# ADC.net
KiCad netlist of a schematic drawn in Altium Designer
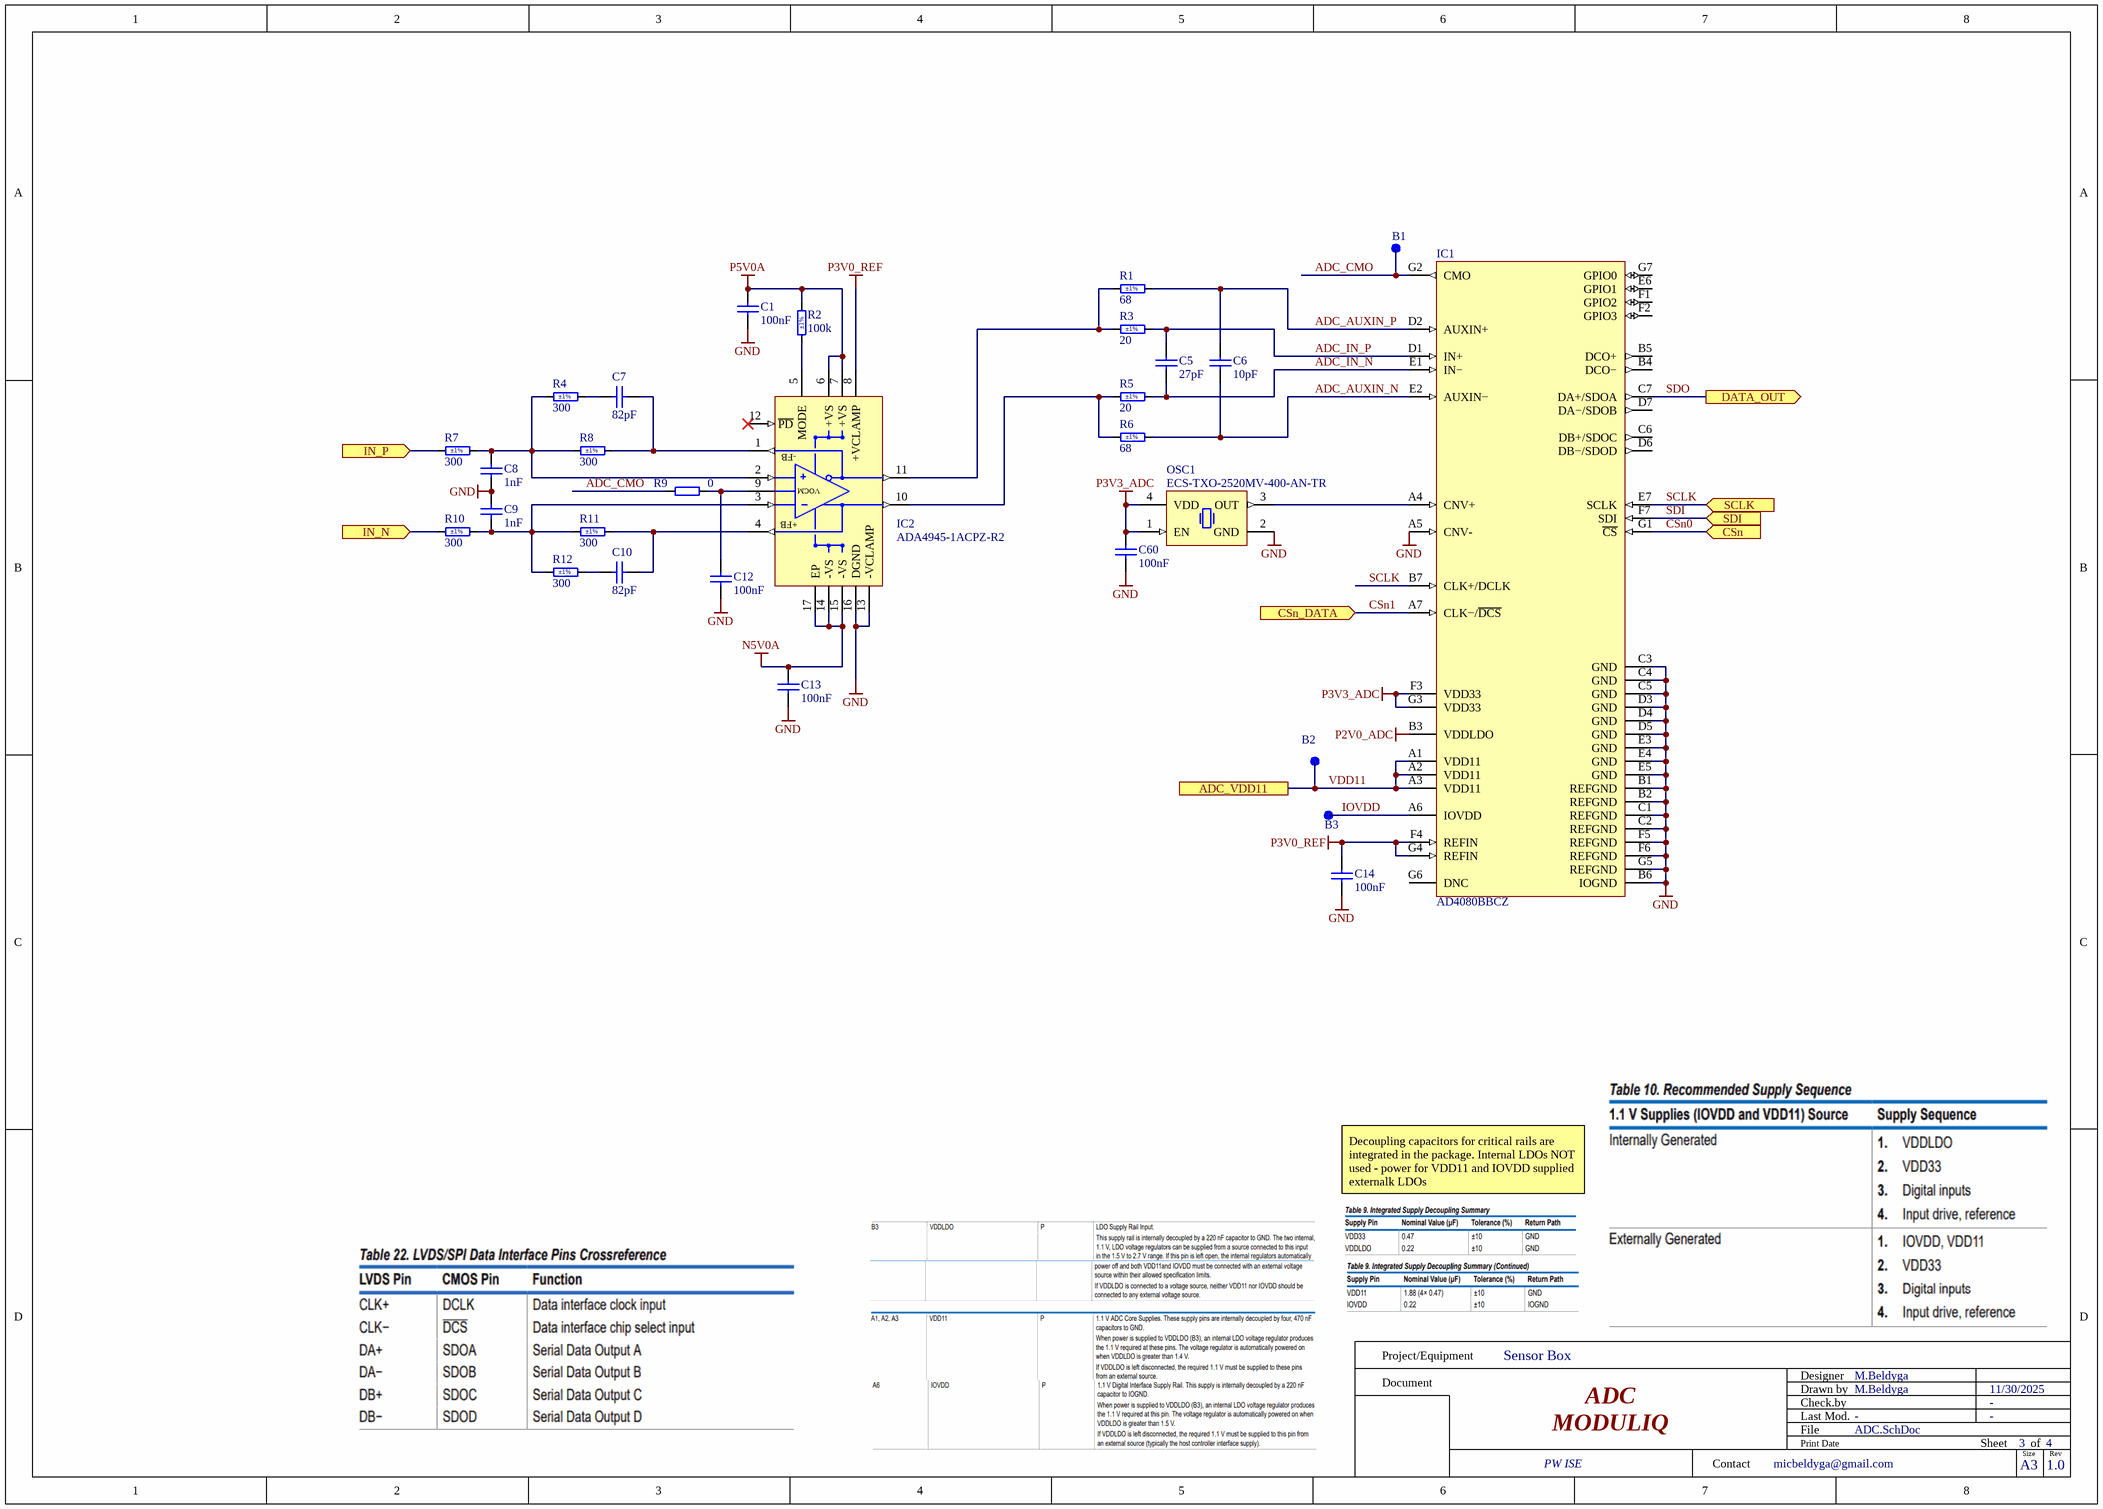
[diagram p0: ADC.SchDoc]

(export (version "E")
  (design (tool "Eeschema 10.0.6"))
  (components
    (comp (ref "B1")
      (value "SMD Pad")
      (footprint "C100")
      (description "Pad")
      (fields (field (name "PART NUMBER") "SMD_PAD_D1MM") (field (name "AUTHOR") "CERN DEM JLC"))
      (libsource (lib "Eletro-mechanical") (part "Single SMD Pad (Round)"))
    )
    (comp (ref "B2")
      (value "SMD Pad")
      (footprint "C100")
      (description "Pad")
      (fields (field (name "PART NUMBER") "SMD_PAD_D1MM") (field (name "AUTHOR") "CERN DEM JLC"))
      (libsource (lib "Eletro-mechanical") (part "Single SMD Pad (Round)"))
    )
    (comp (ref "B3")
      (value "SMD Pad")
      (footprint "C100")
      (description "Pad")
      (fields (field (name "PART NUMBER") "SMD_PAD_D1MM") (field (name "AUTHOR") "CERN DEM JLC"))
      (libsource (lib "Eletro-mechanical") (part "Single SMD Pad (Round)"))
    )
    (comp (ref "C1")
      (value "100nF")
      (footprint "CAPC1005X55N")
      (description "Non-polarised capacitor")
      (fields
        (field (name "PART NUMBER") "CC0402_100NF_50V_10%_X7R")
        (field (name "VOLTAGE") "50V")
        (field (name "AUTHOR") "CERN DEM MR")
      )
      (libsource (lib "Capacitors") (part "Capacitor - non polarized"))
    )
    (comp (ref "C5")
      (value "27pF")
      (footprint "CAPC1005X55N")
      (description "Non-polarised capacitor")
      (fields
        (field (name "PART NUMBER") "CC0402_27PF_50V_5%_C0G")
        (field (name "VOLTAGE") "50V")
        (field (name "AUTHOR") "CERN DEM JLC")
      )
      (libsource (lib "Capacitors") (part "Capacitor - non polarized"))
    )
    (comp (ref "C6")
      (value "10pF")
      (footprint "CAPC1005X55N")
      (description "Non-polarised capacitor")
      (fields
        (field (name "PART NUMBER") "CC0402_10PF_50V_5%_C0G")
        (field (name "VOLTAGE") "50V")
        (field (name "AUTHOR") "CERN DEM JLC")
      )
      (libsource (lib "Capacitors") (part "Capacitor - non polarized"))
    )
    (comp (ref "C7")
      (value "82pF")
      (footprint "CAPC1005X55N")
      (description "Non-polarised capacitor")
      (fields
        (field (name "PART NUMBER") "CC0402_82PF_25V_1%_C0G_KEMET_HiQ-CBR")
        (field (name "VOLTAGE") "25V")
        (field (name "AUTHOR") "CERN DEM MR")
      )
      (libsource (lib "Capacitors") (part "Capacitor - non polarized"))
    )
    (comp (ref "C8")
      (value "1nF")
      (footprint "CAPC1005X55N")
      (description "Non-polarised capacitor")
      (fields
        (field (name "PART NUMBER") "CC0402_1NF_50V_5%_C0G")
        (field (name "VOLTAGE") "50V")
        (field (name "AUTHOR") "CERN DEM BC")
      )
      (libsource (lib "Capacitors") (part "Capacitor - non polarized"))
    )
    (comp (ref "C9")
      (value "1nF")
      (footprint "CAPC1005X55N")
      (description "Non-polarised capacitor")
      (fields
        (field (name "PART NUMBER") "CC0402_1NF_50V_5%_C0G")
        (field (name "VOLTAGE") "50V")
        (field (name "AUTHOR") "CERN DEM BC")
      )
      (libsource (lib "Capacitors") (part "Capacitor - non polarized"))
    )
    (comp (ref "C10")
      (value "82pF")
      (footprint "CAPC1005X55N")
      (description "Non-polarised capacitor")
      (fields
        (field (name "PART NUMBER") "CC0402_82PF_25V_1%_C0G_KEMET_HiQ-CBR")
        (field (name "VOLTAGE") "25V")
        (field (name "AUTHOR") "CERN DEM MR")
      )
      (libsource (lib "Capacitors") (part "Capacitor - non polarized"))
    )
    (comp (ref "C12")
      (value "100nF")
      (footprint "CAPC1005X55N")
      (description "Non-polarised capacitor")
      (fields
        (field (name "PART NUMBER") "CC0402_100NF_50V_10%_X7R")
        (field (name "VOLTAGE") "50V")
        (field (name "AUTHOR") "CERN DEM MR")
      )
      (libsource (lib "Capacitors") (part "Capacitor - non polarized"))
    )
    (comp (ref "C13")
      (value "100nF")
      (footprint "CAPC1005X55N")
      (description "Non-polarised capacitor")
      (fields
        (field (name "PART NUMBER") "CC0402_100NF_50V_10%_X7R")
        (field (name "VOLTAGE") "50V")
        (field (name "AUTHOR") "CERN DEM MR")
      )
      (libsource (lib "Capacitors") (part "Capacitor - non polarized"))
    )
    (comp (ref "C14")
      (value "100nF")
      (footprint "CAPC1005X55N")
      (description "Non-polarised capacitor")
      (fields
        (field (name "PART NUMBER") "CC0402_100NF_50V_10%_X7R")
        (field (name "VOLTAGE") "50V")
        (field (name "AUTHOR") "CERN DEM MR")
      )
      (libsource (lib "Capacitors") (part "Capacitor - non polarized"))
    )
    (comp (ref "C60")
      (value "100nF")
      (footprint "CAPC1005X55N")
      (description "Non-polarised capacitor")
      (fields
        (field (name "PART NUMBER") "CC0402_100NF_50V_10%_X7R")
        (field (name "VOLTAGE") "50V")
        (field (name "AUTHOR") "CERN DEM MR")
      )
      (libsource (lib "Capacitors") (part "Capacitor - non polarized"))
    )
    (comp (ref "IC1")
      (value "AD4080BBCZ")
      (footprint "BGA49C65P7X7_500X500X138")
      (description "20-Bit, 40 MSPS, Differential SAR ADC")
      (fields (field (name "MANUFACTURER") "Analog Devices") (field (name "AUTHOR") "Michal Beldyga"))
      (libsource (lib "Semiconductors") (part "AD4080"))
    )
    (comp (ref "IC2")
      (value "ADA4945-1ACPZ-R2")
      (footprint "QFN50P300X300X80_HS-17N")
      (description "High Speed, ±0.1 µV/˚C Offset Drift, Fully Differential ADC Driver")
      (fields (field (name "MANUFACTURER") "Analog Devices") (field (name "AUTHOR") "Michal Beldyga"))
      (libsource (lib "Semiconductors") (part "ADA4945-1"))
    )
    (comp (ref "OSC1")
      (value "ECS-TXO-2520MV-400-AN-TR")
      (footprint "OSC_QANTEK_QX2")
      (fields (field (name "MANUFACTURER") "ECS International"))
      (libsource (lib "mb") (part "ECS-TXO-2520MV-400-AN-TR"))
    )
    (comp (ref "R1")
      (value "68")
      (footprint "RESC1005X40N")
      (description "Resistor - 1%")
      (fields
        (field (name "TOLERANCE") "±1%")
        (field (name "PART NUMBER") "R0402_68R_1%_0.0625W_100PPM")
        (field (name "POWER") "0.0625W")
        (field (name "AUTHOR") "CERN DEM JLC")
      )
      (libsource (lib "Resistors") (part "Resistor - 1%"))
    )
    (comp (ref "R2")
      (value "100k")
      (footprint "RESC1005X40N")
      (description "Resistor - 1%")
      (fields
        (field (name "TOLERANCE") "±1%")
        (field (name "PART NUMBER") "R0402_100K_1%_0.0625W_100PPM")
        (field (name "POWER") "0.0625W")
        (field (name "AUTHOR") "CERN DEM JLC")
      )
      (libsource (lib "Resistors") (part "Resistor - 1%"))
    )
    (comp (ref "R3")
      (value "20")
      (footprint "RESC1005X40N")
      (description "Resistor - 1%")
      (fields
        (field (name "TOLERANCE") "±1%")
        (field (name "PART NUMBER") "R0402_20R_1%_0.0625W_100PPM")
        (field (name "POWER") "0.0625W")
        (field (name "AUTHOR") "CERN DEM JLC")
      )
      (libsource (lib "Resistors") (part "Resistor - 1%"))
    )
    (comp (ref "R4")
      (value "300")
      (footprint "RESC1005X40N")
      (description "Resistor - 1%")
      (fields
        (field (name "TOLERANCE") "±1%")
        (field (name "PART NUMBER") "R0402_300R_1%_0.0625W_100PPM")
        (field (name "POWER") "0.0625W")
        (field (name "AUTHOR") "CERN DEM JLC")
      )
      (libsource (lib "Resistors") (part "Resistor - 1%"))
    )
    (comp (ref "R5")
      (value "20")
      (footprint "RESC1005X40N")
      (description "Resistor - 1%")
      (fields
        (field (name "TOLERANCE") "±1%")
        (field (name "PART NUMBER") "R0402_20R_1%_0.0625W_100PPM")
        (field (name "POWER") "0.0625W")
        (field (name "AUTHOR") "CERN DEM JLC")
      )
      (libsource (lib "Resistors") (part "Resistor - 1%"))
    )
    (comp (ref "R6")
      (value "68")
      (footprint "RESC1005X40N")
      (description "Resistor - 1%")
      (fields
        (field (name "TOLERANCE") "±1%")
        (field (name "PART NUMBER") "R0402_68R_1%_0.0625W_100PPM")
        (field (name "POWER") "0.0625W")
        (field (name "AUTHOR") "CERN DEM JLC")
      )
      (libsource (lib "Resistors") (part "Resistor - 1%"))
    )
    (comp (ref "R7")
      (value "300")
      (footprint "RESC1005X40N")
      (description "Resistor - 1%")
      (fields
        (field (name "TOLERANCE") "±1%")
        (field (name "PART NUMBER") "R0402_300R_1%_0.0625W_100PPM")
        (field (name "POWER") "0.0625W")
        (field (name "AUTHOR") "CERN DEM JLC")
      )
      (libsource (lib "Resistors") (part "Resistor - 1%"))
    )
    (comp (ref "R8")
      (value "300")
      (footprint "RESC1005X40N")
      (description "Resistor - 1%")
      (fields
        (field (name "TOLERANCE") "±1%")
        (field (name "PART NUMBER") "R0402_300R_1%_0.0625W_100PPM")
        (field (name "POWER") "0.0625W")
        (field (name "AUTHOR") "CERN DEM JLC")
      )
      (libsource (lib "Resistors") (part "Resistor - 1%"))
    )
    (comp (ref "R9")
      (value "0")
      (footprint "RESC1005X40N")
      (description "Resistor")
      (fields
        (field (name "PART NUMBER") "R0402_0R_JUMPER")
        (field (name "MANUFACTURER") "GENERIC")
        (field (name "AUTHOR") "CERN DEM JLC")
      )
      (libsource (lib "Resistors") (part "Resistor"))
    )
    (comp (ref "R10")
      (value "300")
      (footprint "RESC1005X40N")
      (description "Resistor - 1%")
      (fields
        (field (name "TOLERANCE") "±1%")
        (field (name "PART NUMBER") "R0402_300R_1%_0.0625W_100PPM")
        (field (name "POWER") "0.0625W")
        (field (name "AUTHOR") "CERN DEM JLC")
      )
      (libsource (lib "Resistors") (part "Resistor - 1%"))
    )
    (comp (ref "R11")
      (value "300")
      (footprint "RESC1005X40N")
      (description "Resistor - 1%")
      (fields
        (field (name "TOLERANCE") "±1%")
        (field (name "PART NUMBER") "R0402_300R_1%_0.0625W_100PPM")
        (field (name "POWER") "0.0625W")
        (field (name "AUTHOR") "CERN DEM JLC")
      )
      (libsource (lib "Resistors") (part "Resistor - 1%"))
    )
    (comp (ref "R12")
      (value "300")
      (footprint "RESC1005X40N")
      (description "Resistor - 1%")
      (fields
        (field (name "TOLERANCE") "±1%")
        (field (name "PART NUMBER") "R0402_300R_1%_0.0625W_100PPM")
        (field (name "POWER") "0.0625W")
        (field (name "AUTHOR") "CERN DEM JLC")
      )
      (libsource (lib "Resistors") (part "Resistor - 1%"))
    )
  )
  (nets
    (net (code "1") (name "/ADC_AUXIN_N") (class "Default")
      (node (ref "C6") (pin "1") (pinfunction "1_1") (pintype "passive"))
      (node (ref "IC1") (pin "E2") (pinfunction "AUXIN−_E2") (pintype "input"))
      (node (ref "R6") (pin "2") (pinfunction "2_2") (pintype "passive"))
    )
    (net (code "2") (name "/ADC_AUXIN_P") (class "Default")
      (node (ref "C6") (pin "2") (pinfunction "2_2") (pintype "passive"))
      (node (ref "IC1") (pin "D2") (pinfunction "AUXIN+_D2") (pintype "input"))
      (node (ref "R1") (pin "2") (pinfunction "2_2") (pintype "passive"))
    )
    (net (code "3") (name "/ADC_CMO") (class "Default")
      (node (ref "B1") (pin "1") (pinfunction "1_1") (pintype "bidirectional"))
      (node (ref "IC1") (pin "G2") (pinfunction "CMO_G2") (pintype "output"))
      (node (ref "R9") (pin "1") (pinfunction "1_1") (pintype "passive"))
    )
    (net (code "4") (name "/ADC_IN_N") (class "Default")
      (node (ref "C5") (pin "1") (pinfunction "1_1") (pintype "passive"))
      (node (ref "IC1") (pin "E1") (pinfunction "IN−_E1") (pintype "input"))
      (node (ref "R5") (pin "2") (pinfunction "2_2") (pintype "passive"))
    )
    (net (code "5") (name "/ADC_IN_P") (class "Default")
      (node (ref "C5") (pin "2") (pinfunction "2_2") (pintype "passive"))
      (node (ref "IC1") (pin "D1") (pinfunction "IN+_D1") (pintype "input"))
      (node (ref "R3") (pin "2") (pinfunction "2_2") (pintype "passive"))
    )
    (net (code "6") (name "/CSn0") (class "Default")
      (node (ref "IC1") (pin "G1") (pinfunction "~{CS}_G1") (pintype "input"))
    )
    (net (code "7") (name "/CSn1") (class "Default")
      (node (ref "IC1") (pin "A7") (pinfunction "CLK−/~{DCS}_A7") (pintype "input"))
    )
    (net (code "8") (name "/IN_N") (class "Default")
      (node (ref "R10") (pin "1") (pinfunction "1_1") (pintype "passive"))
    )
    (net (code "9") (name "/IN_P") (class "Default")
      (node (ref "R7") (pin "1") (pinfunction "1_1") (pintype "passive"))
    )
    (net (code "10") (name "/IOVDD") (class "Default")
      (node (ref "B3") (pin "1") (pinfunction "1_1") (pintype "bidirectional"))
      (node (ref "IC1") (pin "A6") (pinfunction "IOVDD_A6") (pintype "power_in"))
    )
    (net (code "11") (name "/SCLK") (class "Default")
      (node (ref "IC1") (pin "B7") (pinfunction "CLK+/DCLK_B7") (pintype "input"))
      (node (ref "IC1") (pin "E7") (pinfunction "SCLK_E7") (pintype "input"))
    )
    (net (code "12") (name "/SDI") (class "Default")
      (node (ref "IC1") (pin "F7") (pinfunction "SDI_F7") (pintype "input"))
    )
    (net (code "13") (name "/SDO") (class "Default")
      (node (ref "IC1") (pin "C7") (pinfunction "DA+/SDOA_C7") (pintype "output"))
    )
    (net (code "14") (name "/VDD11") (class "Default")
      (node (ref "B2") (pin "1") (pinfunction "1_1") (pintype "bidirectional"))
      (node (ref "IC1") (pin "A1") (pinfunction "VDD11_A1") (pintype "power_in"))
      (node (ref "IC1") (pin "A2") (pinfunction "VDD11_A2") (pintype "power_in"))
      (node (ref "IC1") (pin "A3") (pinfunction "VDD11_A3") (pintype "power_in"))
    )
    (net (code "15") (name "GND") (class "Default")
      (node (ref "C1") (pin "1") (pinfunction "1_1") (pintype "passive"))
      (node (ref "C12") (pin "1") (pinfunction "1_1") (pintype "passive"))
      (node (ref "C13") (pin "1") (pinfunction "1_1") (pintype "passive"))
      (node (ref "C14") (pin "1") (pinfunction "1_1") (pintype "passive"))
      (node (ref "C60") (pin "1") (pinfunction "1_1") (pintype "passive"))
      (node (ref "C8") (pin "1") (pinfunction "1_1") (pintype "passive"))
      (node (ref "C9") (pin "2") (pinfunction "2_2") (pintype "passive"))
      (node (ref "IC1") (pin "A5") (pinfunction "CNV-_A5") (pintype "input"))
      (node (ref "IC1") (pin "B1") (pinfunction "REFGND_B1") (pintype "power_in"))
      (node (ref "IC1") (pin "B2") (pinfunction "REFGND_B2") (pintype "power_in"))
      (node (ref "IC1") (pin "B6") (pinfunction "IOGND_B6") (pintype "power_in"))
      (node (ref "IC1") (pin "C1") (pinfunction "REFGND_C1") (pintype "power_in"))
      (node (ref "IC1") (pin "C2") (pinfunction "REFGND_C2") (pintype "power_in"))
      (node (ref "IC1") (pin "C3") (pinfunction "GND_C3") (pintype "power_in"))
      (node (ref "IC1") (pin "C4") (pinfunction "GND_C4") (pintype "power_in"))
      (node (ref "IC1") (pin "C5") (pinfunction "GND_C5") (pintype "power_in"))
      (node (ref "IC1") (pin "D3") (pinfunction "GND_D3") (pintype "power_in"))
      (node (ref "IC1") (pin "D4") (pinfunction "GND_D4") (pintype "power_in"))
      (node (ref "IC1") (pin "D5") (pinfunction "GND_D5") (pintype "power_in"))
      (node (ref "IC1") (pin "E3") (pinfunction "GND_E3") (pintype "power_in"))
      (node (ref "IC1") (pin "E4") (pinfunction "GND_E4") (pintype "power_in"))
      (node (ref "IC1") (pin "E5") (pinfunction "GND_E5") (pintype "power_in"))
      (node (ref "IC1") (pin "F5") (pinfunction "REFGND_F5") (pintype "power_in"))
      (node (ref "IC1") (pin "F6") (pinfunction "REFGND_F6") (pintype "power_in"))
      (node (ref "IC1") (pin "G5") (pinfunction "REFGND_G5") (pintype "power_in"))
      (node (ref "IC2") (pin "13") (pinfunction "-VCLAMP_13") (pintype "power_in"))
      (node (ref "IC2") (pin "16") (pinfunction "DGND_16") (pintype "power_in"))
      (node (ref "OSC1") (pin "2") (pinfunction "GND_2") (pintype "power_in"))
    )
    (net (code "16") (name "N5V0A") (class "Default")
      (node (ref "C13") (pin "2") (pinfunction "2_2") (pintype "passive"))
      (node (ref "IC2") (pin "14") (pinfunction "-VS_14") (pintype "power_in"))
      (node (ref "IC2") (pin "15") (pinfunction "-VS_15") (pintype "power_in"))
      (node (ref "IC2") (pin "17") (pinfunction "EP_17") (pintype "power_in"))
    )
    (net (code "17") (name "Net-(C7-Pad1)") (class "Default")
      (node (ref "C7") (pin "1") (pinfunction "1_1") (pintype "passive"))
      (node (ref "R4") (pin "2") (pinfunction "2_2") (pintype "passive"))
    )
    (net (code "18") (name "Net-(C10-Pad1)") (class "Default")
      (node (ref "C10") (pin "1") (pinfunction "1_1") (pintype "passive"))
      (node (ref "R12") (pin "2") (pinfunction "2_2") (pintype "passive"))
    )
    (net (code "19") (name "Net-(IC1-CNV+)") (class "Default")
      (node (ref "IC1") (pin "A4") (pinfunction "CNV+_A4") (pintype "input"))
      (node (ref "OSC1") (pin "3") (pinfunction "OUT_3") (pintype "output"))
    )
    (net (code "20") (name "Net-(IC2-+FB)") (class "Default")
      (node (ref "C10") (pin "2") (pinfunction "2_2") (pintype "passive"))
      (node (ref "IC2") (pin "4") (pinfunction "+FB_4") (pintype "output"))
      (node (ref "R11") (pin "2") (pinfunction "2_2") (pintype "passive"))
    )
    (net (code "21") (name "Net-(IC2-+IN)") (class "Default")
      (node (ref "C8") (pin "2") (pinfunction "2_2") (pintype "passive"))
      (node (ref "IC2") (pin "2") (pinfunction "+IN_2") (pintype "input"))
      (node (ref "R4") (pin "1") (pinfunction "1_1") (pintype "passive"))
      (node (ref "R7") (pin "2") (pinfunction "2_2") (pintype "passive"))
      (node (ref "R8") (pin "1") (pinfunction "1_1") (pintype "passive"))
    )
    (net (code "22") (name "Net-(IC2-+OUT)") (class "Default")
      (node (ref "IC2") (pin "10") (pinfunction "+OUT_10") (pintype "output"))
      (node (ref "R5") (pin "1") (pinfunction "1_1") (pintype "passive"))
      (node (ref "R6") (pin "1") (pinfunction "1_1") (pintype "passive"))
    )
    (net (code "23") (name "Net-(IC2--FB)") (class "Default")
      (node (ref "C7") (pin "2") (pinfunction "2_2") (pintype "passive"))
      (node (ref "IC2") (pin "1") (pinfunction "-FB_1") (pintype "output"))
      (node (ref "R8") (pin "2") (pinfunction "2_2") (pintype "passive"))
    )
    (net (code "24") (name "Net-(IC2--IN)") (class "Default")
      (node (ref "C9") (pin "1") (pinfunction "1_1") (pintype "passive"))
      (node (ref "IC2") (pin "3") (pinfunction "-IN_3") (pintype "input"))
      (node (ref "R10") (pin "2") (pinfunction "2_2") (pintype "passive"))
      (node (ref "R11") (pin "1") (pinfunction "1_1") (pintype "passive"))
      (node (ref "R12") (pin "1") (pinfunction "1_1") (pintype "passive"))
    )
    (net (code "25") (name "Net-(IC2--OUT)") (class "Default")
      (node (ref "IC2") (pin "11") (pinfunction "-OUT_11") (pintype "output"))
      (node (ref "R1") (pin "1") (pinfunction "1_1") (pintype "passive"))
      (node (ref "R3") (pin "1") (pinfunction "1_1") (pintype "passive"))
    )
    (net (code "26") (name "Net-(IC2-MODE)") (class "Default")
      (node (ref "IC2") (pin "5") (pinfunction "MODE_5") (pintype "power_in"))
      (node (ref "R2") (pin "1") (pinfunction "1_1") (pintype "passive"))
    )
    (net (code "27") (name "Net-(IC2-VOCM)") (class "Default")
      (node (ref "C12") (pin "2") (pinfunction "2_2") (pintype "passive"))
      (node (ref "IC2") (pin "9") (pinfunction "VOCM_9") (pintype "passive"))
      (node (ref "R9") (pin "2") (pinfunction "2_2") (pintype "passive"))
    )
    (net (code "28") (name "P2V0_ADC") (class "Default")
      (node (ref "IC1") (pin "B3") (pinfunction "VDDLDO_B3") (pintype "power_in"))
    )
    (net (code "29") (name "P3V0_REF") (class "Default")
      (node (ref "C14") (pin "2") (pinfunction "2_2") (pintype "passive"))
      (node (ref "IC1") (pin "F4") (pinfunction "REFIN_F4") (pintype "input"))
      (node (ref "IC1") (pin "G4") (pinfunction "REFIN_G4") (pintype "input"))
      (node (ref "IC2") (pin "8") (pinfunction "+VCLAMP_8") (pintype "power_in"))
    )
    (net (code "30") (name "P3V3_ADC") (class "Default")
      (node (ref "C60") (pin "2") (pinfunction "2_2") (pintype "passive"))
      (node (ref "IC1") (pin "F3") (pinfunction "VDD33_F3") (pintype "power_in"))
      (node (ref "IC1") (pin "G3") (pinfunction "VDD33_G3") (pintype "power_in"))
      (node (ref "OSC1") (pin "1") (pinfunction "EN_1") (pintype "input"))
      (node (ref "OSC1") (pin "4") (pinfunction "VDD_4") (pintype "power_in"))
    )
    (net (code "31") (name "P5V0A") (class "Default")
      (node (ref "C1") (pin "2") (pinfunction "2_2") (pintype "passive"))
      (node (ref "IC2") (pin "6") (pinfunction "+VS_6") (pintype "power_in"))
      (node (ref "IC2") (pin "7") (pinfunction "+VS_7") (pintype "power_in"))
      (node (ref "R2") (pin "2") (pinfunction "2_2") (pintype "passive"))
    )
    (net (code "32") (name "unconnected-(IC1-DA−{slash}SDOB-PadD7)") (class "Default")
      (node (ref "IC1") (pin "D7") (pinfunction "DA−/SDOB_D7") (pintype "output"))
    )
    (net (code "33") (name "unconnected-(IC1-DB+{slash}SDOC-PadC6)") (class "Default")
      (node (ref "IC1") (pin "C6") (pinfunction "DB+/SDOC_C6") (pintype "output"))
    )
    (net (code "34") (name "unconnected-(IC1-DB−{slash}SDOD-PadD6)") (class "Default")
      (node (ref "IC1") (pin "D6") (pinfunction "DB−/SDOD_D6") (pintype "output"))
    )
    (net (code "35") (name "unconnected-(IC1-DCO+-PadB5)") (class "Default")
      (node (ref "IC1") (pin "B5") (pinfunction "DCO+_B5") (pintype "output"))
    )
    (net (code "36") (name "unconnected-(IC1-DCO−-PadB4)") (class "Default")
      (node (ref "IC1") (pin "B4") (pinfunction "DCO−_B4") (pintype "output"))
    )
    (net (code "37") (name "unconnected-(IC1-DNC-PadG6)") (class "Default")
      (node (ref "IC1") (pin "G6") (pinfunction "DNC_G6") (pintype "passive"))
    )
    (net (code "38") (name "unconnected-(IC1-GPIO0-PadG7)") (class "Default")
      (node (ref "IC1") (pin "G7") (pinfunction "GPIO0_G7") (pintype "bidirectional"))
    )
    (net (code "39") (name "unconnected-(IC1-GPIO1-PadE6)") (class "Default")
      (node (ref "IC1") (pin "E6") (pinfunction "GPIO1_E6") (pintype "bidirectional"))
    )
    (net (code "40") (name "unconnected-(IC1-GPIO2-PadF1)") (class "Default")
      (node (ref "IC1") (pin "F1") (pinfunction "GPIO2_F1") (pintype "bidirectional"))
    )
    (net (code "41") (name "unconnected-(IC1-GPIO3-PadF2)") (class "Default")
      (node (ref "IC1") (pin "F2") (pinfunction "GPIO3_F2") (pintype "bidirectional"))
    )
    (net (code "42") (name "unconnected-(IC2-~{PD}-Pad12)") (class "Default")
      (node (ref "IC2") (pin "12") (pinfunction "~{PD}_12") (pintype "input+no_connect"))
    )
  )
)
